# Power.net
KiCad netlist of a schematic drawn in Altium Designer
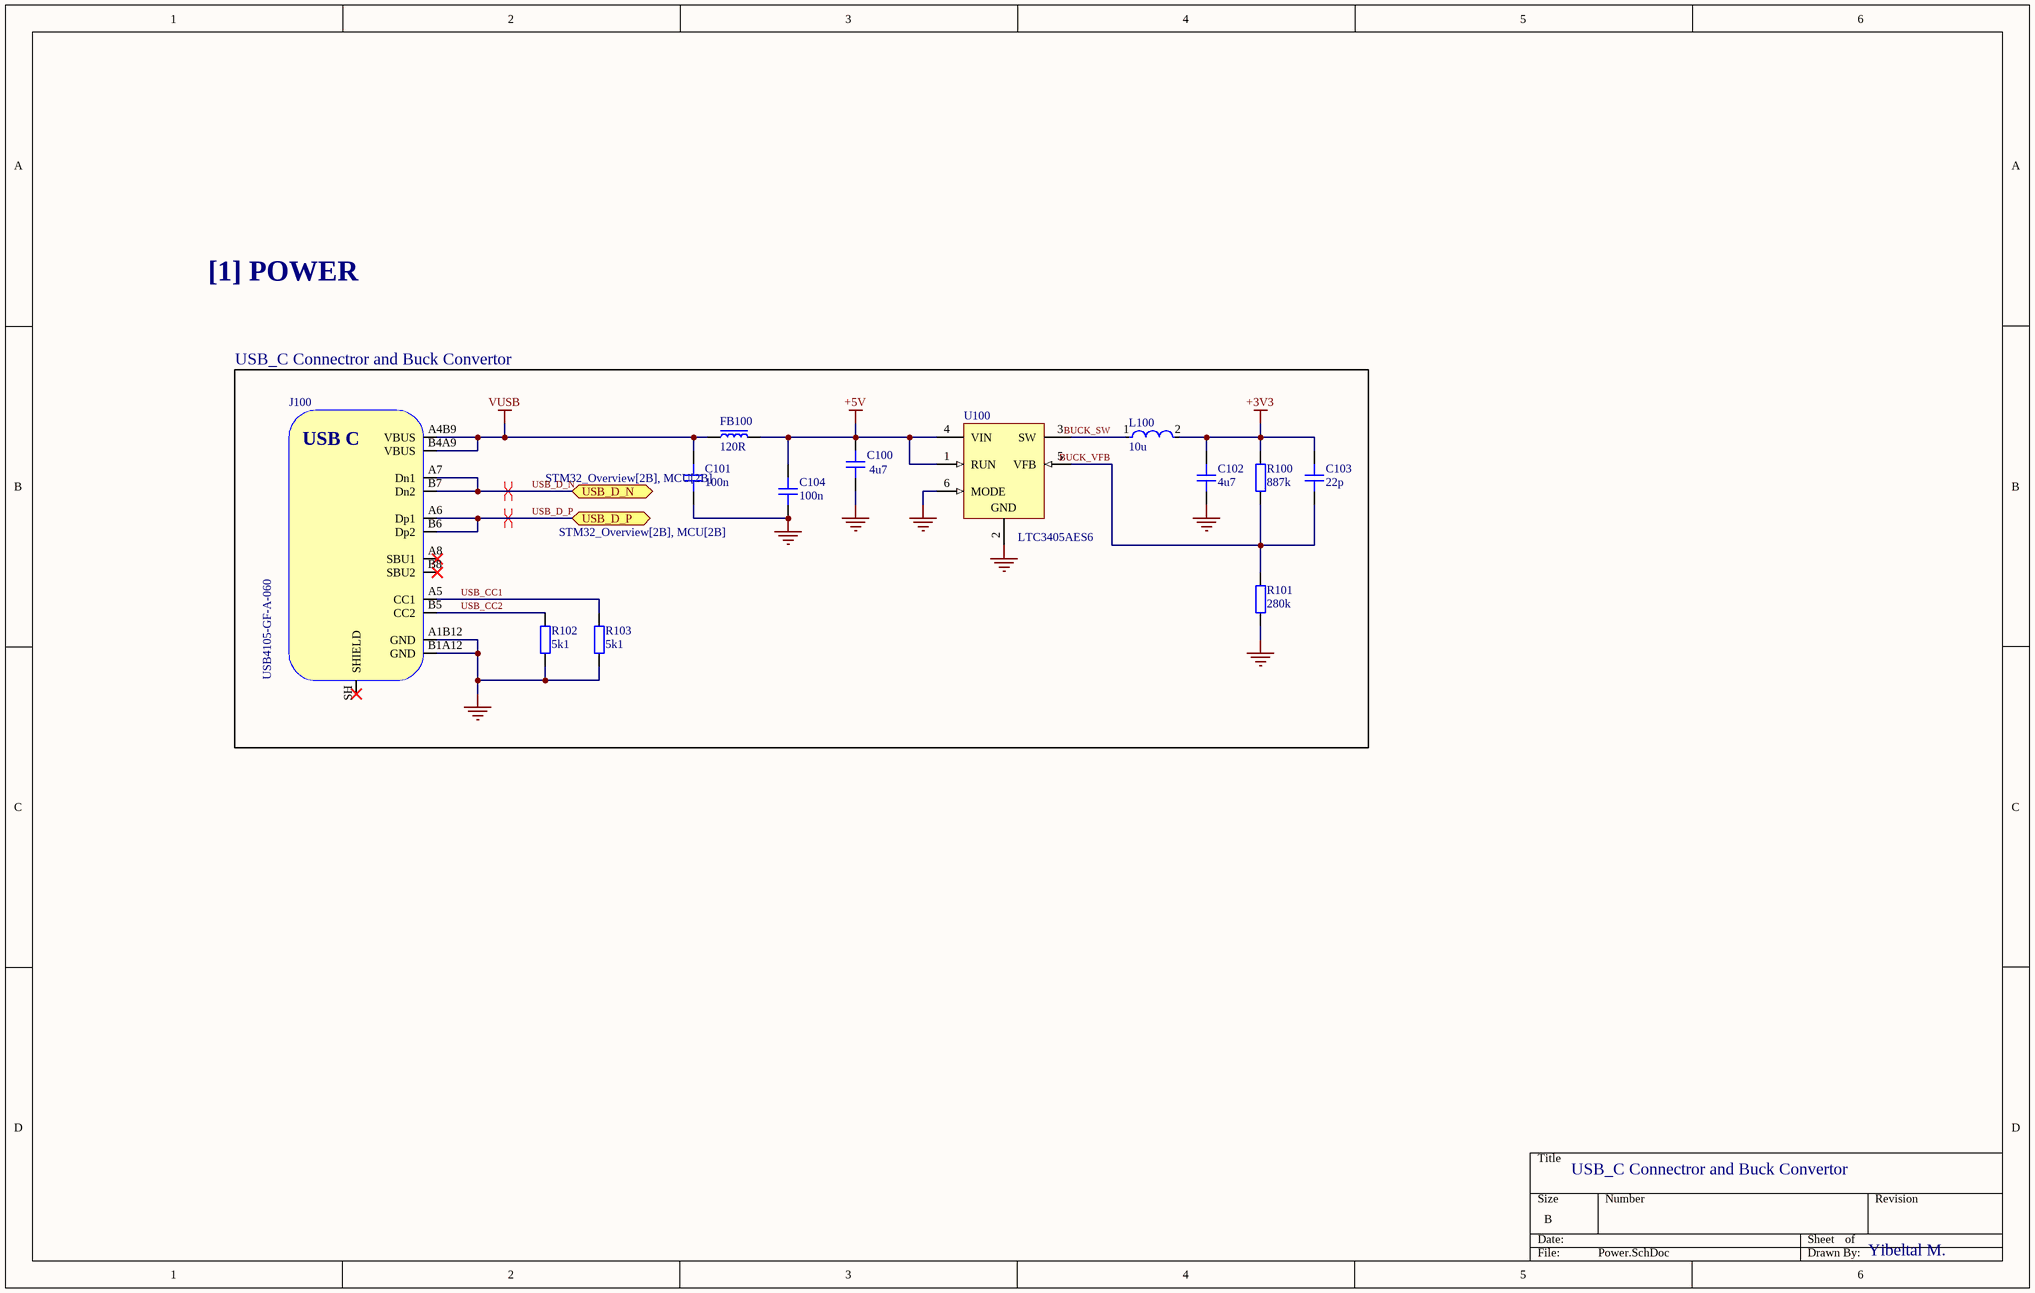
[diagram p0: Power.SchDoc]

(export (version "E")
  (design (tool "Eeschema 10.0.6"))
  (components
    (comp (ref "C100")
      (value "4u7")
      (footprint "CAP_0805")
      (description "Capacitor SMD 0805")
      (libsource (lib "Schematic-Lib-PhilsLab (2)") (part "CAP_0805"))
    )
    (comp (ref "C101")
      (value "100n")
      (footprint "CAP_0805")
      (description "Capacitor SMD 0805")
      (libsource (lib "Schematic-Lib-PhilsLab (2)") (part "CAP_0805"))
    )
    (comp (ref "C102")
      (value "4u7")
      (footprint "CAP_0805")
      (description "Capacitor SMD 0805")
      (libsource (lib "Schematic-Lib-PhilsLab (2)") (part "CAP_0805"))
    )
    (comp (ref "C103")
      (value "22p")
      (footprint "CAP_0805")
      (description "Capacitor SMD 0805")
      (libsource (lib "Schematic-Lib-PhilsLab (2)") (part "CAP_0805"))
    )
    (comp (ref "C104")
      (value "100n")
      (footprint "CAP_0805")
      (description "Capacitor SMD 0805")
      (libsource (lib "Schematic-Lib-PhilsLab (2)") (part "CAP_0805"))
    )
    (comp (ref "FB100")
      (value "120R")
      (footprint "FB_0603")
      (description "Ferrite Bead SMD 0603")
      (libsource (lib "Schematic-Lib-PhilsLab (2)") (part "FB_0603"))
    )
    (comp (ref "J100")
      (value "USB4105-GF-A-060")
      (footprint "USB4105-GF-A-060")
      (description "USB Connector Type C SMT 12 Pin")
      (fields (field (name "MANUFACTURER") "GCT"))
      (libsource (lib "Schematic-Lib-PhilsLab (2)") (part "USB4105-GF-A-060"))
    )
    (comp (ref "L100")
      (value "10u")
      (footprint "FP-NRH2412-MFG")
      (description "Shielded Wirewound Inductor 10uH 20% 0.51A 0.72Ω SMD")
      (fields (field (name "TOLERANCE") "20%"))
      (libsource (lib "Altium Content Vault") (part "725321dda6339637d4d059423bc1c3c"))
    )
    (comp (ref "R100")
      (value "887k")
      (footprint "RES_0603")
      (description "Resistor SMD 0603")
      (libsource (lib "Schematic-Lib-PhilsLab (2)") (part "RES_0603"))
    )
    (comp (ref "R101")
      (value "280k")
      (footprint "RES_0603")
      (description "Resistor SMD 0603")
      (libsource (lib "Schematic-Lib-PhilsLab (2)") (part "RES_0603"))
    )
    (comp (ref "R102")
      (value "5k1")
      (footprint "RES_0603")
      (description "Resistor SMD 0603")
      (libsource (lib "Schematic-Lib-PhilsLab (2)") (part "RES_0603"))
    )
    (comp (ref "R103")
      (value "5k1")
      (footprint "RES_0603")
      (description "Resistor SMD 0603")
      (libsource (lib "Schematic-Lib-PhilsLab (2)") (part "RES_0603"))
    )
    (comp (ref "U100")
      (value "LTC3405AES6")
      (footprint "LT-S6-6-TSOT-23_L")
      (fields
        (field (name "PARTNUMBER") "LTC3405AES6#TRMPBF")
        (field (name "MANUFACTURER") "Linear Technology")
      )
      (libsource (lib "Altium Content Vault") (part "LT-LTC3405A-S6-6"))
    )
  )
  (nets
    (net (code "1") (name "+3V3") (class "Default")
      (node (ref "C102") (pin "2") (pinfunction "2_2") (pintype "passive"))
      (node (ref "C103") (pin "2") (pinfunction "2_2") (pintype "passive"))
      (node (ref "L100") (pin "2") (pinfunction "2_2") (pintype "passive"))
      (node (ref "R100") (pin "2") (pinfunction "2_2") (pintype "passive"))
    )
    (net (code "2") (name "+5V") (class "Default")
      (node (ref "C100") (pin "2") (pinfunction "2_2") (pintype "passive"))
      (node (ref "C104") (pin "2") (pinfunction "2_2") (pintype "passive"))
      (node (ref "FB100") (pin "2") (pinfunction "2_2") (pintype "passive"))
      (node (ref "U100") (pin "1") (pinfunction "RUN_1") (pintype "input"))
      (node (ref "U100") (pin "4") (pinfunction "VIN_4") (pintype "power_in"))
    )
    (net (code "3") (name "/BUCK_SW") (class "Default")
      (node (ref "L100") (pin "1") (pinfunction "1_1") (pintype "passive"))
      (node (ref "U100") (pin "3") (pinfunction "SW_3") (pintype "power_in"))
    )
    (net (code "4") (name "/BUCK_VFB") (class "Default")
      (node (ref "C103") (pin "1") (pinfunction "1_1") (pintype "passive"))
      (node (ref "R100") (pin "1") (pinfunction "1_1") (pintype "passive"))
      (node (ref "R101") (pin "2") (pinfunction "2_2") (pintype "passive"))
      (node (ref "U100") (pin "5") (pinfunction "VFB_5") (pintype "input"))
    )
    (net (code "5") (name "/USB_CC1") (class "Default")
      (node (ref "J100") (pin "A5") (pinfunction "CC1_A5") (pintype "passive"))
      (node (ref "R103") (pin "2") (pinfunction "2_2") (pintype "passive"))
    )
    (net (code "6") (name "/USB_CC2") (class "Default")
      (node (ref "J100") (pin "B5") (pinfunction "CC2_B5") (pintype "passive"))
      (node (ref "R102") (pin "2") (pinfunction "2_2") (pintype "passive"))
    )
    (net (code "7") (name "/USB_D_N") (class "Default")
      (node (ref "J100") (pin "A7") (pinfunction "Dn1_A7") (pintype "passive"))
      (node (ref "J100") (pin "B7") (pinfunction "Dn2_B7") (pintype "passive"))
    )
    (net (code "8") (name "/USB_D_P") (class "Default")
      (node (ref "J100") (pin "A6") (pinfunction "Dp1_A6") (pintype "passive"))
      (node (ref "J100") (pin "B6") (pinfunction "Dp2_B6") (pintype "passive"))
    )
    (net (code "9") (name "GND") (class "Default")
      (node (ref "C100") (pin "1") (pinfunction "1_1") (pintype "passive"))
      (node (ref "C101") (pin "1") (pinfunction "1_1") (pintype "passive"))
      (node (ref "C102") (pin "1") (pinfunction "1_1") (pintype "passive"))
      (node (ref "C104") (pin "1") (pinfunction "1_1") (pintype "passive"))
      (node (ref "J100") (pin "A1B12") (pinfunction "GND_A1B12") (pintype "passive"))
      (node (ref "J100") (pin "B1A12") (pinfunction "GND_B1A12") (pintype "passive"))
      (node (ref "R101") (pin "1") (pinfunction "1_1") (pintype "passive"))
      (node (ref "R102") (pin "1") (pinfunction "1_1") (pintype "passive"))
      (node (ref "R103") (pin "1") (pinfunction "1_1") (pintype "passive"))
      (node (ref "U100") (pin "2") (pinfunction "GND_2") (pintype "power_in"))
      (node (ref "U100") (pin "6") (pinfunction "MODE_6") (pintype "input"))
    )
    (net (code "10") (name "VUSB") (class "Default")
      (node (ref "C101") (pin "2") (pinfunction "2_2") (pintype "passive"))
      (node (ref "FB100") (pin "1") (pinfunction "1_1") (pintype "passive"))
      (node (ref "J100") (pin "A4B9") (pinfunction "VBUS_A4B9") (pintype "passive"))
      (node (ref "J100") (pin "B4A9") (pinfunction "VBUS_B4A9") (pintype "passive"))
    )
    (net (code "11") (name "unconnected-(J100-SBU1-PadA8)") (class "Default")
      (node (ref "J100") (pin "A8") (pinfunction "SBU1_A8") (pintype "passive+no_connect"))
    )
    (net (code "12") (name "unconnected-(J100-SBU2-PadB8)") (class "Default")
      (node (ref "J100") (pin "B8") (pinfunction "SBU2_B8") (pintype "passive+no_connect"))
    )
    (net (code "13") (name "unconnected-(J100-SHIELD-PadSH)") (class "Default")
      (node (ref "J100") (pin "SH") (pinfunction "SHIELD_SH") (pintype "passive+no_connect"))
    )
  )
)
